# controllo_livello_serbatoio_acqua.net
KiCad netlist of a schematic drawn in EAGLE
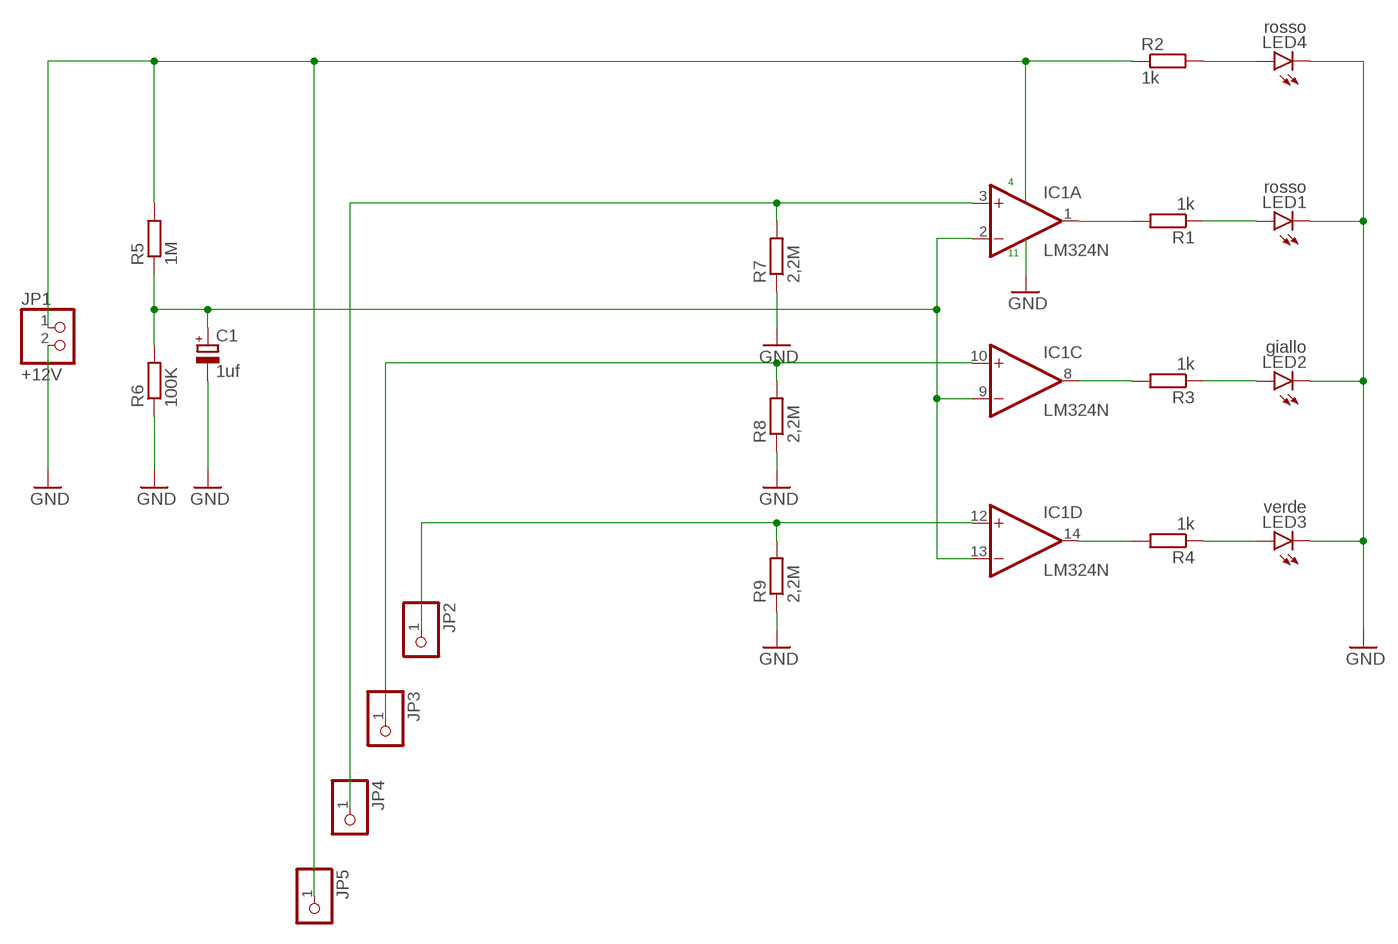
[diagram p0: schematic, sheet 1]

(export (version "E")
  (design (tool "Eeschema 10.0.6"))
  (components
    (comp (ref "C1")
      (value "1uf")
      (footprint "eagle-import:E2,5-5")
      (libsource (lib "eagle-import") (part "CPOL-EUE2.5-5"))
    )
    (comp (ref "IC1")
      (value "LM324N")
      (footprint "eagle-import:DIL14")
      (libsource (lib "eagle-import") (part "LM324N"))
    )
    (comp (ref "JP1")
      (value "+12V")
      (footprint "eagle-import:1X02")
      (libsource (lib "eagle-import") (part "PINHD-1X2"))
    )
    (comp (ref "JP2")
      (value "PINHD-1X1")
      (footprint "eagle-import:1X01")
      (libsource (lib "eagle-import") (part "PINHD-1X1"))
    )
    (comp (ref "JP3")
      (value "PINHD-1X1")
      (footprint "eagle-import:1X01")
      (libsource (lib "eagle-import") (part "PINHD-1X1"))
    )
    (comp (ref "JP4")
      (value "PINHD-1X1")
      (footprint "eagle-import:1X01")
      (libsource (lib "eagle-import") (part "PINHD-1X1"))
    )
    (comp (ref "JP5")
      (value "PINHD-1X1")
      (footprint "eagle-import:1X01")
      (libsource (lib "eagle-import") (part "PINHD-1X1"))
    )
    (comp (ref "LED1")
      (value "rosso")
      (footprint "eagle-import:LED3MM")
      (libsource (lib "eagle-import") (part "LED3MM"))
    )
    (comp (ref "LED2")
      (value "giallo")
      (footprint "eagle-import:LED3MM")
      (libsource (lib "eagle-import") (part "LED3MM"))
    )
    (comp (ref "LED3")
      (value "verde")
      (footprint "eagle-import:LED3MM")
      (libsource (lib "eagle-import") (part "LED3MM"))
    )
    (comp (ref "LED4")
      (value "rosso")
      (footprint "eagle-import:LED3MM")
      (libsource (lib "eagle-import") (part "LED3MM"))
    )
    (comp (ref "R1")
      (value "1k")
      (footprint "eagle-import:0207_10")
      (libsource (lib "eagle-import") (part "R-EU_0207/10"))
    )
    (comp (ref "R2")
      (value "1k")
      (footprint "eagle-import:0207_10")
      (libsource (lib "eagle-import") (part "R-EU_0207/10"))
    )
    (comp (ref "R3")
      (value "1k")
      (footprint "eagle-import:0207_10")
      (libsource (lib "eagle-import") (part "R-EU_0207/10"))
    )
    (comp (ref "R4")
      (value "1k")
      (footprint "eagle-import:0207_10")
      (libsource (lib "eagle-import") (part "R-EU_0207/10"))
    )
    (comp (ref "R5")
      (value "1M")
      (footprint "eagle-import:0207_10")
      (libsource (lib "eagle-import") (part "R-EU_0207/10"))
    )
    (comp (ref "R6")
      (value "100K")
      (footprint "eagle-import:0207_10")
      (libsource (lib "eagle-import") (part "R-EU_0207/10"))
    )
    (comp (ref "R7")
      (value "2,2M")
      (footprint "eagle-import:0207_10")
      (libsource (lib "eagle-import") (part "R-EU_0207/10"))
    )
    (comp (ref "R8")
      (value "2,2M")
      (footprint "eagle-import:0207_10")
      (libsource (lib "eagle-import") (part "R-EU_0207/10"))
    )
    (comp (ref "R9")
      (value "2,2M")
      (footprint "eagle-import:0207_10")
      (libsource (lib "eagle-import") (part "R-EU_0207/10"))
    )
  )
  (nets
    (net (code "1") (name "GND") (class "Default")
      (node (ref "C1") (pin "-") (pinfunction "-_-") (pintype "passive"))
      (node (ref "JP1") (pin "2") (pinfunction "2_2") (pintype "passive"))
      (node (ref "LED1") (pin "K") (pinfunction "C_K") (pintype "passive"))
      (node (ref "LED2") (pin "K") (pinfunction "C_K") (pintype "passive"))
      (node (ref "LED3") (pin "K") (pinfunction "C_K") (pintype "passive"))
      (node (ref "LED4") (pin "K") (pinfunction "C_K") (pintype "passive"))
      (node (ref "R6") (pin "1") (pinfunction "1_1") (pintype "passive"))
      (node (ref "R7") (pin "1") (pinfunction "1_1") (pintype "passive"))
      (node (ref "R8") (pin "1") (pinfunction "1_1") (pintype "passive"))
      (node (ref "R9") (pin "1") (pinfunction "1_1") (pintype "passive"))
    )
    (net (code "2") (name "Net-(IC1A-+IN)") (class "Default")
      (node (ref "IC1") (pin "3") (pinfunction "+IN_3") (pintype "input"))
      (node (ref "JP4") (pin "1") (pinfunction "1_1") (pintype "passive"))
      (node (ref "R7") (pin "2") (pinfunction "2_2") (pintype "passive"))
    )
    (net (code "3") (name "Net-(IC1A--IN)") (class "Default")
      (node (ref "C1") (pin "+") (pinfunction "+_+") (pintype "passive"))
      (node (ref "IC1") (pin "13") (pinfunction "-IN_13") (pintype "input"))
      (node (ref "IC1") (pin "2") (pinfunction "-IN_2") (pintype "input"))
      (node (ref "IC1") (pin "9") (pinfunction "-IN_9") (pintype "input"))
      (node (ref "R5") (pin "1") (pinfunction "1_1") (pintype "passive"))
      (node (ref "R6") (pin "2") (pinfunction "2_2") (pintype "passive"))
    )
    (net (code "4") (name "Net-(IC1A-OUT)") (class "Default")
      (node (ref "IC1") (pin "1") (pinfunction "OUT_1") (pintype "output"))
      (node (ref "R1") (pin "2") (pinfunction "2_2") (pintype "passive"))
    )
    (net (code "5") (name "Net-(IC1C-+IN)") (class "Default")
      (node (ref "IC1") (pin "10") (pinfunction "+IN_10") (pintype "input"))
      (node (ref "JP3") (pin "1") (pinfunction "1_1") (pintype "passive"))
      (node (ref "R8") (pin "2") (pinfunction "2_2") (pintype "passive"))
    )
    (net (code "6") (name "Net-(IC1C-OUT)") (class "Default")
      (node (ref "IC1") (pin "8") (pinfunction "OUT_8") (pintype "output"))
      (node (ref "R3") (pin "2") (pinfunction "2_2") (pintype "passive"))
    )
    (net (code "7") (name "Net-(IC1D-+IN)") (class "Default")
      (node (ref "IC1") (pin "12") (pinfunction "+IN_12") (pintype "input"))
      (node (ref "JP2") (pin "1") (pinfunction "1_1") (pintype "passive"))
      (node (ref "R9") (pin "2") (pinfunction "2_2") (pintype "passive"))
    )
    (net (code "8") (name "Net-(IC1D-OUT)") (class "Default")
      (node (ref "IC1") (pin "14") (pinfunction "OUT_14") (pintype "output"))
      (node (ref "R4") (pin "2") (pinfunction "2_2") (pintype "passive"))
    )
    (net (code "9") (name "Net-(JP1-Pad1)") (class "Default")
      (node (ref "JP1") (pin "1") (pinfunction "1_1") (pintype "passive"))
      (node (ref "JP5") (pin "1") (pinfunction "1_1") (pintype "passive"))
      (node (ref "R2") (pin "1") (pinfunction "1_1") (pintype "passive"))
      (node (ref "R5") (pin "2") (pinfunction "2_2") (pintype "passive"))
    )
    (net (code "10") (name "Net-(LED1-PadA)") (class "Default")
      (node (ref "LED1") (pin "A") (pinfunction "A_A") (pintype "passive"))
      (node (ref "R1") (pin "1") (pinfunction "1_1") (pintype "passive"))
    )
    (net (code "11") (name "Net-(LED2-PadA)") (class "Default")
      (node (ref "LED2") (pin "A") (pinfunction "A_A") (pintype "passive"))
      (node (ref "R3") (pin "1") (pinfunction "1_1") (pintype "passive"))
    )
    (net (code "12") (name "Net-(LED3-PadA)") (class "Default")
      (node (ref "LED3") (pin "A") (pinfunction "A_A") (pintype "passive"))
      (node (ref "R4") (pin "1") (pinfunction "1_1") (pintype "passive"))
    )
    (net (code "13") (name "Net-(LED4-PadA)") (class "Default")
      (node (ref "LED4") (pin "A") (pinfunction "A_A") (pintype "passive"))
      (node (ref "R2") (pin "2") (pinfunction "2_2") (pintype "passive"))
    )
  )
)
